# USBpowconn.net
KiCad netlist of a schematic drawn in EAGLE
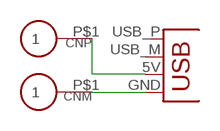
[diagram p0: schematic, sheet 1]

(export (version "E")
  (design (tool "Eeschema 10.0.6"))
  (components
    (comp (ref "CNM")
      (value "CON_P01TH09MM")
      (footprint "eagle-import:PAD_TH09MM")
      (libsource (lib "eagle-import") (part "CON_P01TH09MM"))
    )
    (comp (ref "CNP")
      (value "CON_P01TH09MM")
      (footprint "eagle-import:PAD_TH09MM")
      (libsource (lib "eagle-import") (part "CON_P01TH09MM"))
    )
    (comp (ref "JP1")
      (value "CON_USBPCB")
      (footprint "eagle-import:USB-A-PCB")
      (libsource (lib "eagle-import") (part "CON_USBPCB"))
    )
  )
  (nets
    (net (code "1") (name "Net-(CNM-1)") (class "Default")
      (node (ref "CNM") (pin "P$1") (pinfunction "1_P$1") (pintype "bidirectional"))
      (node (ref "JP1") (pin "GND") (pinfunction "GND_GND") (pintype "bidirectional"))
    )
    (net (code "2") (name "Net-(CNP-1)") (class "Default")
      (node (ref "CNP") (pin "P$1") (pinfunction "1_P$1") (pintype "bidirectional"))
      (node (ref "JP1") (pin "5V") (pinfunction "VBUS_5V") (pintype "bidirectional"))
    )
    (net (code "3") (name "unconnected-(JP1-D+-PadUSB_P)") (class "Default")
      (node (ref "JP1") (pin "USB_P") (pinfunction "D+_USB_P") (pintype "bidirectional"))
    )
    (net (code "4") (name "unconnected-(JP1-D--PadUSB_M)") (class "Default")
      (node (ref "JP1") (pin "USB_M") (pinfunction "D-_USB_M") (pintype "bidirectional"))
    )
  )
)
